# 09_USB_HUB.net
KiCad netlist of a schematic drawn in Altium Designer
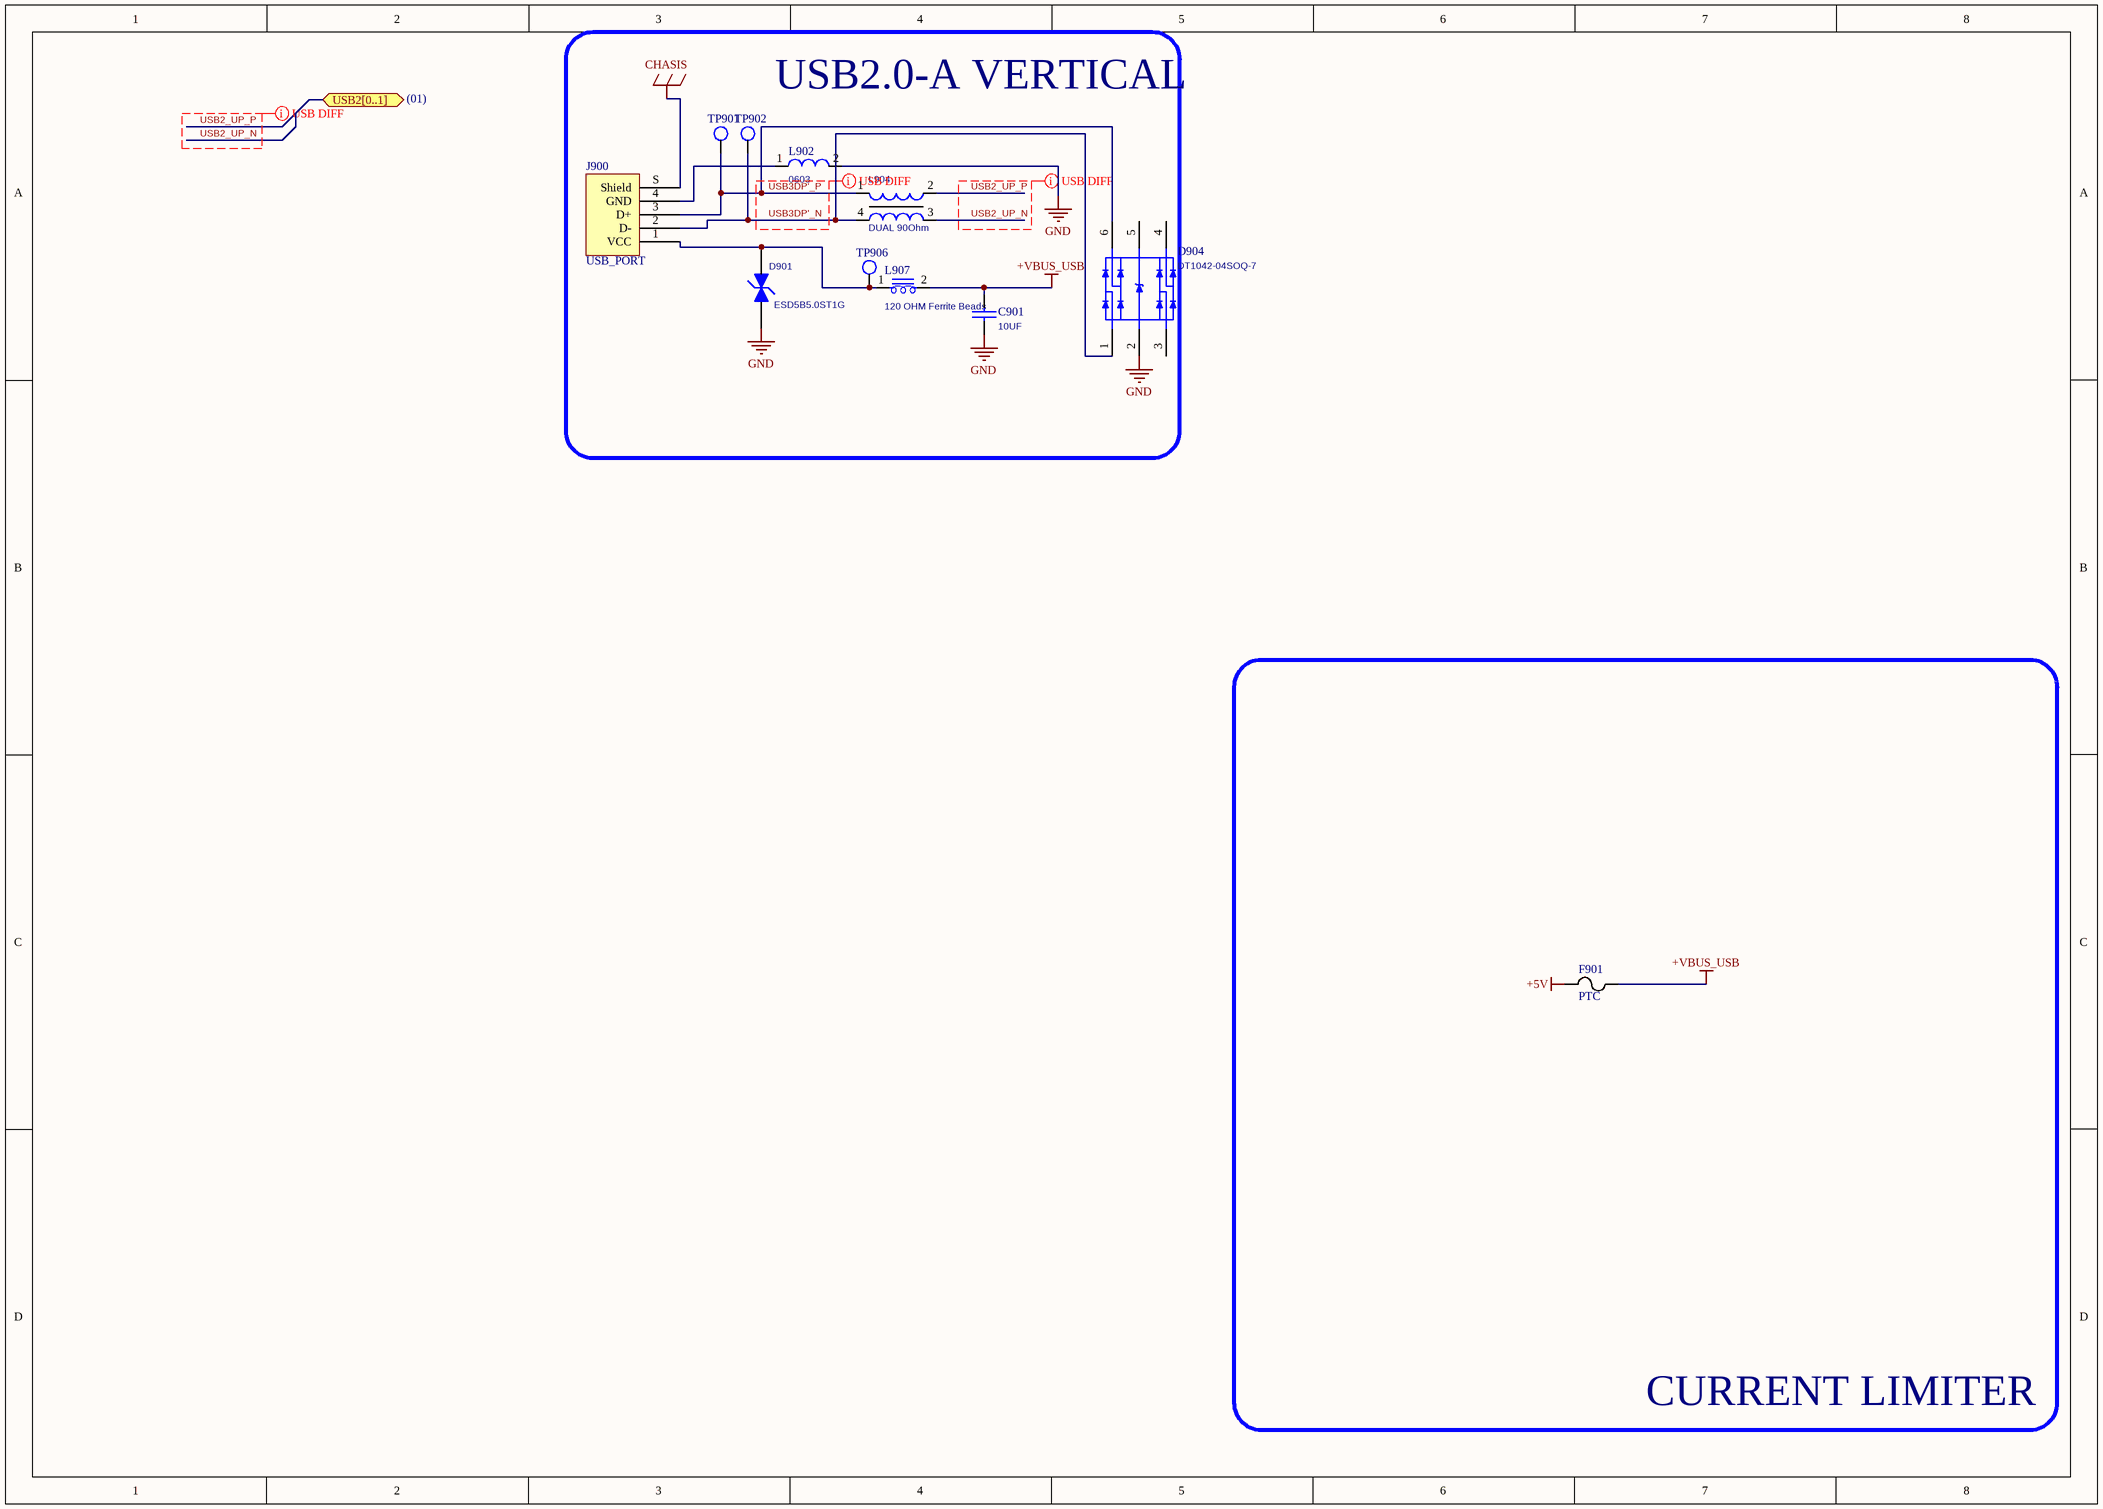
[diagram p0: 09 USB HUB.SchDoc]

(export (version "E")
  (design (tool "Eeschema 10.0.6"))
  (components
    (comp (ref "C901")
      (value "10UF")
      (footprint "0805")
      (description "CAP CER 10UF 16V X5R 0805")
      (fields (field (name "CREATED BY") "EE") (field (name "CHECKED BY") "*"))
      (libsource (lib "ARETE_SCH") (part "CAP-CL21A106KOQNNNG"))
    )
    (comp (ref "D901")
      (value "ESD5B5.0ST1G")
      (footprint "SOD523 - SZESD")
      (description "VS DIODE 5V SOD523")
      (fields (field (name "CREATED BY") "E.E") (field (name "CHECKED BY") "*"))
      (libsource (lib "ARETE_SCH") (part "DIODE-ESD5B5.0ST1G"))
    )
    (comp (ref "D904")
      (value "DT1042-04SOQ-7")
      (footprint "DIODE-DT1042-04SOQ-7")
      (description "HDMI TVS DIODE")
      (fields (field (name "CREATED BY") "E.E") (field (name "CHECKED BY") "*"))
      (libsource (lib "ARETE_SCH") (part "DIODE-DT1042-04SOQ-7"))
    )
    (comp (ref "F901")
      (value "PTC")
      (footprint "1812")
      (description "THERMISTOR PTC RESETTABLE FUSE 1206 1100mA 33V 1812")
      (fields (field (name "CREATED BY") "EE") (field (name "CHECKED BY") "*"))
      (libsource (lib "ARETE_V2_SCH") (part "FUSE-KMC5S110RY33"))
    )
    (comp (ref "J900")
      (value "USB_PORT")
      (footprint "ON SHORE TECHNOLOGY USB-A1HSW6")
      (description "CONN RCPT TYPEA 4POS R/A")
      (fields
        (field (name "PART NUMBER") "USB-A1HSW6")
        (field (name "MANUFACTURER") "On Shore Technology Inc.")
      )
      (libsource (lib "Celestial Altium Library - altium_library") (part "USB 2.0 TYPE A"))
    )
    (comp (ref "L902")
      (value "0603")
      (footprint "0603_RES")
      (description "0OHM 0603")
      (fields (field (name "CREATED BY") "EE") (field (name "CHECKED BY") "*"))
      (libsource (lib "ARETE_SCH") (part "IND-FERRITE (RES 0 OHM) 0603"))
    )
    (comp (ref "L904")
      (value "DUAL 90Ohm")
      (footprint "DLW21H")
      (description "Common Mode Chokes Dual 90Ohm 100MHz 0.33A 0.35Ohm DCR SMD T/R")
      (fields (field (name "CREATED BY") "E.E") (field (name "CHECKED BY") "*"))
      (libsource (lib "ARETE_SCH") (part "IND-DLW21HN900SQ2L"))
    )
    (comp (ref "L907")
      (value "120 OHM Ferrite Beads")
      (footprint "0603_RES")
      (description "Ferrite Beads Multi-Layer 120Ohm 25% 100MHz 2A 0.05Ohm DCR 0603 Automotive T/R")
      (fields (field (name "CREATED BY") "E.E") (field (name "CHECKED BY") "*"))
      (libsource (lib "ARETE_SCH") (part "IND-BLM18PG121SH1D"))
    )
    (comp (ref "TP901")
      (value "TEST POINT 15")
      (footprint "testpoint_15")
      (libsource (lib "ARETE_L") (part "TEST POINT 15"))
    )
    (comp (ref "TP902")
      (value "TEST POINT 15")
      (footprint "testpoint_15")
      (libsource (lib "ARETE_L") (part "TEST POINT 15"))
    )
    (comp (ref "TP906")
      (value "TEST POINT 15")
      (footprint "testpoint_15")
      (libsource (lib "ARETE_L") (part "TEST POINT 15"))
    )
  )
  (nets
    (net (code "3") (name "+5V") (class "Default")
      (node (ref "F901") (pin "1") (pinfunction "1_1") (pintype "passive"))
    )
    (net (code "4") (name "+VBUS_USB") (class "Default")
      (node (ref "C901") (pin "1") (pinfunction "1_1") (pintype "passive"))
      (node (ref "F901") (pin "2") (pinfunction "2_2") (pintype "passive"))
      (node (ref "L907") (pin "2") (pinfunction "2_2") (pintype "passive"))
    )
    (net (code "6") (name "/USB2_UP_N") (class "Default")
      (node (ref "L904") (pin "3") (pinfunction "3_3") (pintype "passive"))
    )
    (net (code "7") (name "/USB2_UP_P") (class "Default")
      (node (ref "L904") (pin "2") (pinfunction "2_2") (pintype "passive"))
    )
    (net (code "8") (name "/USB3DP'_N") (class "Default")
      (node (ref "D904") (pin "1") (pinfunction "IO1_1") (pintype "passive"))
      (node (ref "J900") (pin "2") (pinfunction "D-_2") (pintype "passive"))
      (node (ref "L904") (pin "4") (pinfunction "4_4") (pintype "passive"))
      (node (ref "TP902") (pin "1") (pinfunction "1_1") (pintype "passive"))
    )
    (net (code "9") (name "/USB3DP'_P") (class "Default")
      (node (ref "D904") (pin "6") (pinfunction "IO4_6") (pintype "passive"))
      (node (ref "J900") (pin "3") (pinfunction "D+_3") (pintype "passive"))
      (node (ref "L904") (pin "1") (pinfunction "1_1") (pintype "passive"))
      (node (ref "TP901") (pin "1") (pinfunction "1_1") (pintype "passive"))
    )
    (net (code "10") (name "CHASIS") (class "Default")
      (node (ref "J900") (pin "S") (pinfunction "Shield_S") (pintype "passive"))
    )
    (net (code "11") (name "GND") (class "Default")
      (node (ref "C901") (pin "2") (pinfunction "2_2") (pintype "passive"))
      (node (ref "D901") (pin "1") (pinfunction "A_1") (pintype "passive"))
      (node (ref "D904") (pin "2") (pinfunction "VSS_2") (pintype "power_in"))
      (node (ref "L902") (pin "2") (pinfunction "2_2") (pintype "passive"))
    )
    (net (code "12") (name "Net-(D901-K)") (class "Default")
      (node (ref "D901") (pin "2") (pinfunction "K_2") (pintype "passive"))
      (node (ref "J900") (pin "1") (pinfunction "VCC_1") (pintype "passive"))
      (node (ref "L907") (pin "1") (pinfunction "1_1") (pintype "passive"))
      (node (ref "TP906") (pin "1") (pinfunction "1_1") (pintype "passive"))
    )
    (net (code "13") (name "Net-(J900-GND)") (class "Default")
      (node (ref "J900") (pin "4") (pinfunction "GND_4") (pintype "passive"))
      (node (ref "L902") (pin "1") (pinfunction "1_1") (pintype "passive"))
    )
    (net (code "14") (name "unconnected-(D904-IO2-Pad3)") (class "Default")
      (node (ref "D904") (pin "3") (pinfunction "IO2_3") (pintype "passive"))
    )
    (net (code "15") (name "unconnected-(D904-IO3-Pad4)") (class "Default")
      (node (ref "D904") (pin "4") (pinfunction "IO3_4") (pintype "passive"))
    )
    (net (code "16") (name "unconnected-(D904-VCC-Pad5)") (class "Default")
      (node (ref "D904") (pin "5") (pinfunction "VCC_5") (pintype "power_in"))
    )
  )
)
